# old_IO_Expanders.net
KiCad netlist of a schematic drawn in Altium Designer
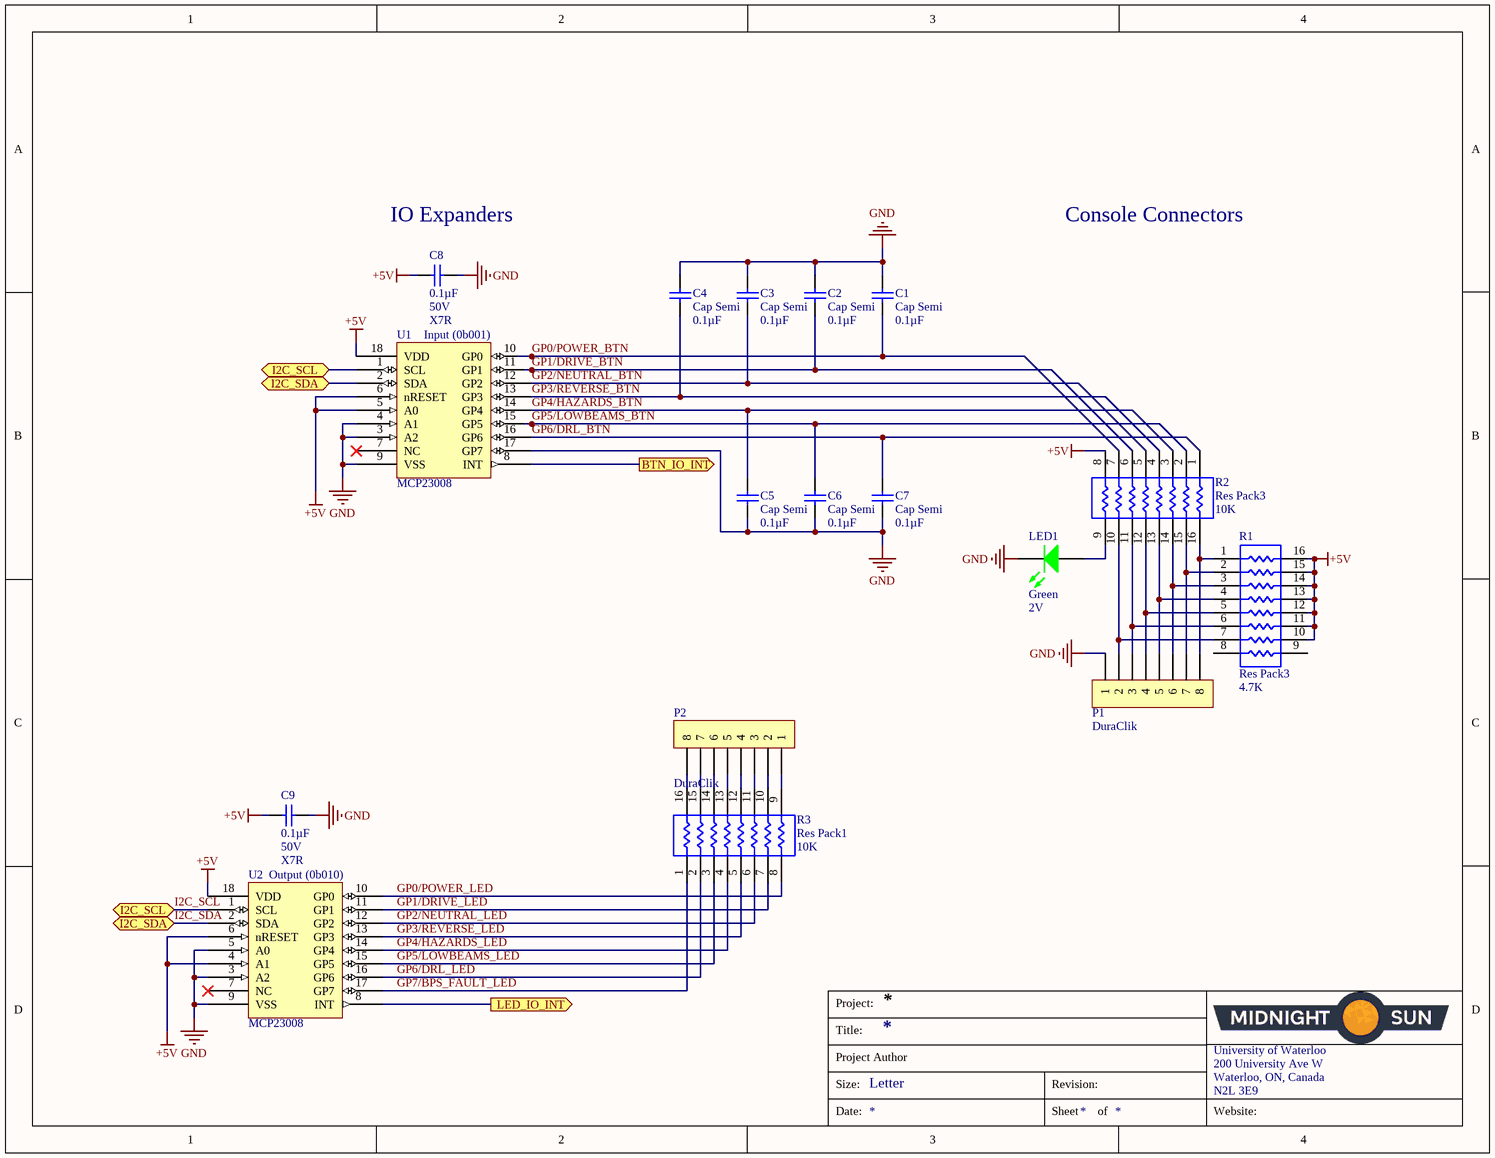
[diagram p0: old_IO_Expanders.SchDoc]

(export (version "E")
  (design (tool "Eeschema 10.0.6"))
  (components
    (comp (ref "C1")
      (value "Cap Semi")
      (footprint "C1206")
      (description "Capacitor (Semiconductor SIM Model)")
      (fields (field (name "ALTIUM_VALUE") "0.1µF") (field (name "PUBLISHER") "Altium Limited"))
      (libsource (lib "Miscellaneous Devices") (part "Cap Semi"))
    )
    (comp (ref "C2")
      (value "Cap Semi")
      (footprint "C1206")
      (description "Capacitor (Semiconductor SIM Model)")
      (fields (field (name "ALTIUM_VALUE") "0.1µF") (field (name "PUBLISHER") "Altium Limited"))
      (libsource (lib "Miscellaneous Devices") (part "Cap Semi"))
    )
    (comp (ref "C3")
      (value "Cap Semi")
      (footprint "C1206")
      (description "Capacitor (Semiconductor SIM Model)")
      (fields (field (name "ALTIUM_VALUE") "0.1µF") (field (name "PUBLISHER") "Altium Limited"))
      (libsource (lib "Miscellaneous Devices") (part "Cap Semi"))
    )
    (comp (ref "C4")
      (value "Cap Semi")
      (footprint "C1206")
      (description "Capacitor (Semiconductor SIM Model)")
      (fields (field (name "ALTIUM_VALUE") "0.1µF") (field (name "PUBLISHER") "Altium Limited"))
      (libsource (lib "Miscellaneous Devices") (part "Cap Semi"))
    )
    (comp (ref "C5")
      (value "Cap Semi")
      (footprint "C1206")
      (description "Capacitor (Semiconductor SIM Model)")
      (fields (field (name "ALTIUM_VALUE") "0.1µF") (field (name "PUBLISHER") "Altium Limited"))
      (libsource (lib "Miscellaneous Devices") (part "Cap Semi"))
    )
    (comp (ref "C6")
      (value "Cap Semi")
      (footprint "C1206")
      (description "Capacitor (Semiconductor SIM Model)")
      (fields (field (name "ALTIUM_VALUE") "0.1µF") (field (name "PUBLISHER") "Altium Limited"))
      (libsource (lib "Miscellaneous Devices") (part "Cap Semi"))
    )
    (comp (ref "C7")
      (value "Cap Semi")
      (footprint "C1206")
      (description "Capacitor (Semiconductor SIM Model)")
      (fields (field (name "ALTIUM_VALUE") "0.1µF") (field (name "PUBLISHER") "Altium Limited"))
      (libsource (lib "Miscellaneous Devices") (part "Cap Semi"))
    )
    (comp (ref "C8")
      (value "CAP CER 0.1UF 50V 10% X7R 0603")
      (footprint "CAP, 0603")
      (description "0.10µF ±10% 50V Ceramic Capacitor X7R 0603 (1608 Metric)")
      (fields
        (field (name "TOLERANCE") "±10%")
        (field (name "CAPACITANCE") "0.1µF")
        (field (name "VOLTAGE") "50V")
        (field (name "TEMPERATURE COEFFICIENT") "X7R")
      )
      (libsource (lib "Schematic Diagrams") (part "CAP CER 0.1UF 50V 10% X7R 0603"))
    )
    (comp (ref "C9")
      (value "CAP CER 0.1UF 50V 10% X7R 0603")
      (footprint "CAP, 0603")
      (description "0.10µF ±10% 50V Ceramic Capacitor X7R 0603 (1608 Metric)")
      (fields
        (field (name "TOLERANCE") "±10%")
        (field (name "CAPACITANCE") "0.1µF")
        (field (name "VOLTAGE") "50V")
        (field (name "TEMPERATURE COEFFICIENT") "X7R")
      )
      (libsource (lib "Schematic Diagrams") (part "CAP CER 0.1UF 50V 10% X7R 0603"))
    )
    (comp (ref "LED1")
      (value "LED GREEN CLEAR 2V 0603")
      (footprint "LED_0603")
      (description "Green 572nm LED Indication - Discrete 2V 0603 (1608 Metric)")
      (fields
        (field (name "MANUFACTURER") "Wurth Electronics Inc.")
        (field (name "MANUFACTURER PART NUMBER") "150060VS75000")
        (field (name "COLOR") "Green")
        (field (name "VOLTAGE - FORWARD (VF) (TYP)") "2V")
      )
      (libsource (lib "Schematic Diagrams") (part "LED GREEN CLEAR 2V 0603"))
    )
    (comp (ref "P1")
      (value "CONN 8POS DURA-CLIK 0.079\"")
      (footprint "CONN, 8POS Dura-Clik")
      (description "8 Positions Header Connector 0.079\" (2.00mm) Surface Mount Tin")
      (fields (field (name "SERIES") "DuraClik"))
      (libsource (lib "Schematic Diagrams") (part "CONN 8POS DURA-CLIK 0.079{dblquote}"))
    )
    (comp (ref "P2")
      (value "CONN 8POS DURA-CLIK 0.079\"")
      (footprint "CONN, 8POS Dura-Clik")
      (description "8 Positions Header Connector 0.079\" (2.00mm) Surface Mount Tin")
      (fields (field (name "SERIES") "DuraClik"))
      (libsource (lib "") (part "CONN 8POS DURA-CLIK 0.079{dblquote}_1"))
    )
    (comp (ref "R1")
      (value "Res Pack3")
      (footprint "SO-16_N")
      (description "Isolated Resistor Network")
      (fields (field (name "ALTIUM_VALUE") "4.7K") (field (name "PUBLISHER") "Altium Limited"))
      (libsource (lib "Miscellaneous Devices") (part "Res Pack3"))
    )
    (comp (ref "R2")
      (value "Res Pack3")
      (footprint "SO-16_N")
      (description "Isolated Resistor Network")
      (fields (field (name "ALTIUM_VALUE") "10K") (field (name "PUBLISHER") "Altium Limited"))
      (libsource (lib "Miscellaneous Devices") (part "Res Pack3"))
    )
    (comp (ref "R3")
      (value "Res Pack1")
      (footprint "SO-16_N")
      (description "Isolated Resistor Network")
      (fields (field (name "ALTIUM_VALUE") "10K") (field (name "PUBLISHER") "Altium Limited"))
      (libsource (lib "Miscellaneous Devices") (part "Res Pack3"))
    )
    (comp (ref "U1")
      (value "MCP23008")
      (footprint "IC 18SOIC")
      (description "MCP23008 I/O Expander 8B+1Int 18P SOIC")
      (fields
        (field (name "MANUFACTURER") "Microchip Technology")
        (field (name "MANUFACTURER PART NUMBER") "MCP23008T-E/SO")
      )
      (libsource (lib "Schematic Diagrams") (part "IC I/O EXPANDER I2C 8B 18SOIC"))
    )
    (comp (ref "U2")
      (value "MCP23008")
      (footprint "IC 18SOIC")
      (description "MCP23008 I/O Expander 8B+1Int 18P SOIC")
      (fields
        (field (name "MANUFACTURER") "Microchip Technology")
        (field (name "MANUFACTURER PART NUMBER") "MCP23008T-E/SO")
      )
      (libsource (lib "Schematic Diagrams") (part "IC I/O EXPANDER I2C 8B 18SOIC"))
    )
  )
  (nets
    (net (code "1") (name "+5V") (class "Default")
      (node (ref "C8") (pin "1") (pinfunction "1_1") (pintype "passive"))
      (node (ref "C9") (pin "1") (pinfunction "1_1") (pintype "passive"))
      (node (ref "R1") (pin "10") (pinfunction "10_10") (pintype "passive"))
      (node (ref "R1") (pin "11") (pinfunction "11_11") (pintype "passive"))
      (node (ref "R1") (pin "12") (pinfunction "12_12") (pintype "passive"))
      (node (ref "R1") (pin "13") (pinfunction "13_13") (pintype "passive"))
      (node (ref "R1") (pin "14") (pinfunction "14_14") (pintype "passive"))
      (node (ref "R1") (pin "15") (pinfunction "15_15") (pintype "passive"))
      (node (ref "R1") (pin "16") (pinfunction "16_16") (pintype "passive"))
      (node (ref "R2") (pin "8") (pinfunction "8_8") (pintype "passive"))
      (node (ref "U1") (pin "18") (pinfunction "VDD_18") (pintype "power_in"))
      (node (ref "U1") (pin "5") (pinfunction "A0_5") (pintype "input"))
      (node (ref "U1") (pin "6") (pinfunction "nRESET_6") (pintype "input"))
      (node (ref "U2") (pin "18") (pinfunction "VDD_18") (pintype "power_in"))
      (node (ref "U2") (pin "4") (pinfunction "A1_4") (pintype "input"))
      (node (ref "U2") (pin "6") (pinfunction "nRESET_6") (pintype "input"))
    )
    (net (code "2") (name "/BTN_IO_INT") (class "Default")
      (node (ref "U1") (pin "8") (pinfunction "INT_8") (pintype "output"))
    )
    (net (code "3") (name "/GP0{slash}POWER_BTN") (class "Default")
      (node (ref "C1") (pin "1") (pinfunction "1_1") (pintype "passive"))
      (node (ref "R2") (pin "7") (pinfunction "7_7") (pintype "passive"))
      (node (ref "U1") (pin "10") (pinfunction "GP0_10") (pintype "bidirectional"))
    )
    (net (code "4") (name "/GP0{slash}POWER_LED") (class "Default")
      (node (ref "R3") (pin "8") (pinfunction "8_8") (pintype "passive"))
      (node (ref "U2") (pin "10") (pinfunction "GP0_10") (pintype "bidirectional"))
    )
    (net (code "5") (name "/GP1{slash}DRIVE_BTN") (class "Default")
      (node (ref "C2") (pin "2") (pinfunction "2_2") (pintype "passive"))
      (node (ref "R2") (pin "6") (pinfunction "6_6") (pintype "passive"))
      (node (ref "U1") (pin "11") (pinfunction "GP1_11") (pintype "bidirectional"))
    )
    (net (code "6") (name "/GP1{slash}DRIVE_LED") (class "Default")
      (node (ref "R3") (pin "7") (pinfunction "7_7") (pintype "passive"))
      (node (ref "U2") (pin "11") (pinfunction "GP1_11") (pintype "bidirectional"))
    )
    (net (code "7") (name "/GP2{slash}NEUTRAL_BTN") (class "Default")
      (node (ref "C3") (pin "2") (pinfunction "2_2") (pintype "passive"))
      (node (ref "R2") (pin "5") (pinfunction "5_5") (pintype "passive"))
      (node (ref "U1") (pin "12") (pinfunction "GP2_12") (pintype "bidirectional"))
    )
    (net (code "8") (name "/GP2{slash}NEUTRAL_LED") (class "Default")
      (node (ref "R3") (pin "6") (pinfunction "6_6") (pintype "passive"))
      (node (ref "U2") (pin "12") (pinfunction "GP2_12") (pintype "bidirectional"))
    )
    (net (code "9") (name "/GP3{slash}REVERSE_BTN") (class "Default")
      (node (ref "C4") (pin "2") (pinfunction "2_2") (pintype "passive"))
      (node (ref "R2") (pin "4") (pinfunction "4_4") (pintype "passive"))
      (node (ref "U1") (pin "13") (pinfunction "GP3_13") (pintype "bidirectional"))
    )
    (net (code "10") (name "/GP3{slash}REVERSE_LED") (class "Default")
      (node (ref "R3") (pin "5") (pinfunction "5_5") (pintype "passive"))
      (node (ref "U2") (pin "13") (pinfunction "GP3_13") (pintype "bidirectional"))
    )
    (net (code "11") (name "/GP4{slash}HAZARDS_BTN") (class "Default")
      (node (ref "C5") (pin "1") (pinfunction "1_1") (pintype "passive"))
      (node (ref "R2") (pin "3") (pinfunction "3_3") (pintype "passive"))
      (node (ref "U1") (pin "14") (pinfunction "GP4_14") (pintype "bidirectional"))
    )
    (net (code "12") (name "/GP4{slash}HAZARDS_LED") (class "Default")
      (node (ref "R3") (pin "4") (pinfunction "4_4") (pintype "passive"))
      (node (ref "U2") (pin "14") (pinfunction "GP4_14") (pintype "bidirectional"))
    )
    (net (code "13") (name "/GP5{slash}LOWBEAMS_BTN") (class "Default")
      (node (ref "C6") (pin "1") (pinfunction "1_1") (pintype "passive"))
      (node (ref "R2") (pin "2") (pinfunction "2_2") (pintype "passive"))
      (node (ref "U1") (pin "15") (pinfunction "GP5_15") (pintype "bidirectional"))
    )
    (net (code "14") (name "/GP5{slash}LOWBEAMS_LED") (class "Default")
      (node (ref "R3") (pin "3") (pinfunction "3_3") (pintype "passive"))
      (node (ref "U2") (pin "15") (pinfunction "GP5_15") (pintype "bidirectional"))
    )
    (net (code "15") (name "/GP6{slash}DRL_BTN") (class "Default")
      (node (ref "C7") (pin "1") (pinfunction "1_1") (pintype "passive"))
      (node (ref "R2") (pin "1") (pinfunction "1_1") (pintype "passive"))
      (node (ref "U1") (pin "16") (pinfunction "GP6_16") (pintype "bidirectional"))
    )
    (net (code "16") (name "/GP6{slash}DRL_LED") (class "Default")
      (node (ref "R3") (pin "2") (pinfunction "2_2") (pintype "passive"))
      (node (ref "U2") (pin "16") (pinfunction "GP6_16") (pintype "bidirectional"))
    )
    (net (code "17") (name "/GP7{slash}BPS_FAULT_LED") (class "Default")
      (node (ref "R3") (pin "1") (pinfunction "1_1") (pintype "passive"))
      (node (ref "U2") (pin "17") (pinfunction "GP7_17") (pintype "bidirectional"))
    )
    (net (code "18") (name "/I2C_SCL") (class "Default")
      (node (ref "U1") (pin "1") (pinfunction "SCL_1") (pintype "bidirectional"))
      (node (ref "U2") (pin "1") (pinfunction "SCL_1") (pintype "bidirectional"))
    )
    (net (code "19") (name "/I2C_SDA") (class "Default")
      (node (ref "U1") (pin "2") (pinfunction "SDA_2") (pintype "bidirectional"))
      (node (ref "U2") (pin "2") (pinfunction "SDA_2") (pintype "bidirectional"))
    )
    (net (code "20") (name "/LED_IO_INT") (class "Default")
      (node (ref "U2") (pin "8") (pinfunction "INT_8") (pintype "output"))
    )
    (net (code "21") (name "GND") (class "Default")
      (node (ref "C1") (pin "2") (pinfunction "2_2") (pintype "passive"))
      (node (ref "C2") (pin "1") (pinfunction "1_1") (pintype "passive"))
      (node (ref "C3") (pin "1") (pinfunction "1_1") (pintype "passive"))
      (node (ref "C4") (pin "1") (pinfunction "1_1") (pintype "passive"))
      (node (ref "C5") (pin "2") (pinfunction "2_2") (pintype "passive"))
      (node (ref "C6") (pin "2") (pinfunction "2_2") (pintype "passive"))
      (node (ref "C7") (pin "2") (pinfunction "2_2") (pintype "passive"))
      (node (ref "C8") (pin "2") (pinfunction "2_2") (pintype "passive"))
      (node (ref "C9") (pin "2") (pinfunction "2_2") (pintype "passive"))
      (node (ref "LED1") (pin "2") (pinfunction "K_2") (pintype "passive"))
      (node (ref "P1") (pin "1") (pinfunction "1_1") (pintype "passive"))
      (node (ref "U1") (pin "17") (pinfunction "GP7_17") (pintype "bidirectional"))
      (node (ref "U1") (pin "3") (pinfunction "A2_3") (pintype "input"))
      (node (ref "U1") (pin "4") (pinfunction "A1_4") (pintype "input"))
      (node (ref "U1") (pin "9") (pinfunction "VSS_9") (pintype "power_in"))
      (node (ref "U2") (pin "3") (pinfunction "A2_3") (pintype "input"))
      (node (ref "U2") (pin "5") (pinfunction "A0_5") (pintype "input"))
      (node (ref "U2") (pin "9") (pinfunction "VSS_9") (pintype "power_in"))
    )
    (net (code "22") (name "Net-(LED1-A)") (class "Default")
      (node (ref "LED1") (pin "1") (pinfunction "A_1") (pintype "passive"))
      (node (ref "R2") (pin "9") (pinfunction "9_9") (pintype "passive"))
    )
    (net (code "23") (name "Net-(P1-Pad2)") (class "Default")
      (node (ref "P1") (pin "2") (pinfunction "2_2") (pintype "passive"))
      (node (ref "R1") (pin "7") (pinfunction "7_7") (pintype "passive"))
      (node (ref "R2") (pin "10") (pinfunction "10_10") (pintype "passive"))
    )
    (net (code "24") (name "Net-(P1-Pad3)") (class "Default")
      (node (ref "P1") (pin "3") (pinfunction "3_3") (pintype "passive"))
      (node (ref "R1") (pin "6") (pinfunction "6_6") (pintype "passive"))
      (node (ref "R2") (pin "11") (pinfunction "11_11") (pintype "passive"))
    )
    (net (code "25") (name "Net-(P1-Pad4)") (class "Default")
      (node (ref "P1") (pin "4") (pinfunction "4_4") (pintype "passive"))
      (node (ref "R1") (pin "5") (pinfunction "5_5") (pintype "passive"))
      (node (ref "R2") (pin "12") (pinfunction "12_12") (pintype "passive"))
    )
    (net (code "26") (name "Net-(P1-Pad5)") (class "Default")
      (node (ref "P1") (pin "5") (pinfunction "5_5") (pintype "passive"))
      (node (ref "R1") (pin "4") (pinfunction "4_4") (pintype "passive"))
      (node (ref "R2") (pin "13") (pinfunction "13_13") (pintype "passive"))
    )
    (net (code "27") (name "Net-(P1-Pad6)") (class "Default")
      (node (ref "P1") (pin "6") (pinfunction "6_6") (pintype "passive"))
      (node (ref "R1") (pin "3") (pinfunction "3_3") (pintype "passive"))
      (node (ref "R2") (pin "14") (pinfunction "14_14") (pintype "passive"))
    )
    (net (code "28") (name "Net-(P1-Pad7)") (class "Default")
      (node (ref "P1") (pin "7") (pinfunction "7_7") (pintype "passive"))
      (node (ref "R1") (pin "2") (pinfunction "2_2") (pintype "passive"))
      (node (ref "R2") (pin "15") (pinfunction "15_15") (pintype "passive"))
    )
    (net (code "29") (name "Net-(P1-Pad8)") (class "Default")
      (node (ref "P1") (pin "8") (pinfunction "8_8") (pintype "passive"))
      (node (ref "R1") (pin "1") (pinfunction "1_1") (pintype "passive"))
      (node (ref "R2") (pin "16") (pinfunction "16_16") (pintype "passive"))
    )
    (net (code "30") (name "Net-(P2-Pad1)") (class "Default")
      (node (ref "P2") (pin "1") (pinfunction "1_1") (pintype "passive"))
      (node (ref "R3") (pin "9") (pinfunction "9_9") (pintype "passive"))
    )
    (net (code "31") (name "Net-(P2-Pad2)") (class "Default")
      (node (ref "P2") (pin "2") (pinfunction "2_2") (pintype "passive"))
      (node (ref "R3") (pin "10") (pinfunction "10_10") (pintype "passive"))
    )
    (net (code "32") (name "Net-(P2-Pad3)") (class "Default")
      (node (ref "P2") (pin "3") (pinfunction "3_3") (pintype "passive"))
      (node (ref "R3") (pin "11") (pinfunction "11_11") (pintype "passive"))
    )
    (net (code "33") (name "Net-(P2-Pad4)") (class "Default")
      (node (ref "P2") (pin "4") (pinfunction "4_4") (pintype "passive"))
      (node (ref "R3") (pin "12") (pinfunction "12_12") (pintype "passive"))
    )
    (net (code "34") (name "Net-(P2-Pad5)") (class "Default")
      (node (ref "P2") (pin "5") (pinfunction "5_5") (pintype "passive"))
      (node (ref "R3") (pin "13") (pinfunction "13_13") (pintype "passive"))
    )
    (net (code "35") (name "Net-(P2-Pad6)") (class "Default")
      (node (ref "P2") (pin "6") (pinfunction "6_6") (pintype "passive"))
      (node (ref "R3") (pin "14") (pinfunction "14_14") (pintype "passive"))
    )
    (net (code "36") (name "Net-(P2-Pad7)") (class "Default")
      (node (ref "P2") (pin "7") (pinfunction "7_7") (pintype "passive"))
      (node (ref "R3") (pin "15") (pinfunction "15_15") (pintype "passive"))
    )
    (net (code "37") (name "Net-(P2-Pad8)") (class "Default")
      (node (ref "P2") (pin "8") (pinfunction "8_8") (pintype "passive"))
      (node (ref "R3") (pin "16") (pinfunction "16_16") (pintype "passive"))
    )
    (net (code "38") (name "unconnected-(R1-Pad8)") (class "Default")
      (node (ref "R1") (pin "8") (pinfunction "8_8") (pintype "passive"))
    )
    (net (code "39") (name "unconnected-(R1-Pad9)") (class "Default")
      (node (ref "R1") (pin "9") (pinfunction "9_9") (pintype "passive"))
    )
    (net (code "40") (name "unconnected-(U1-NC-Pad7)") (class "Default")
      (node (ref "U1") (pin "7") (pinfunction "NC_7") (pintype "passive+no_connect"))
    )
    (net (code "41") (name "unconnected-(U2-NC-Pad7)") (class "Default")
      (node (ref "U2") (pin "7") (pinfunction "NC_7") (pintype "passive+no_connect"))
    )
  )
)
